# Controler_2_25.net
KiCad netlist of a schematic drawn in EAGLE
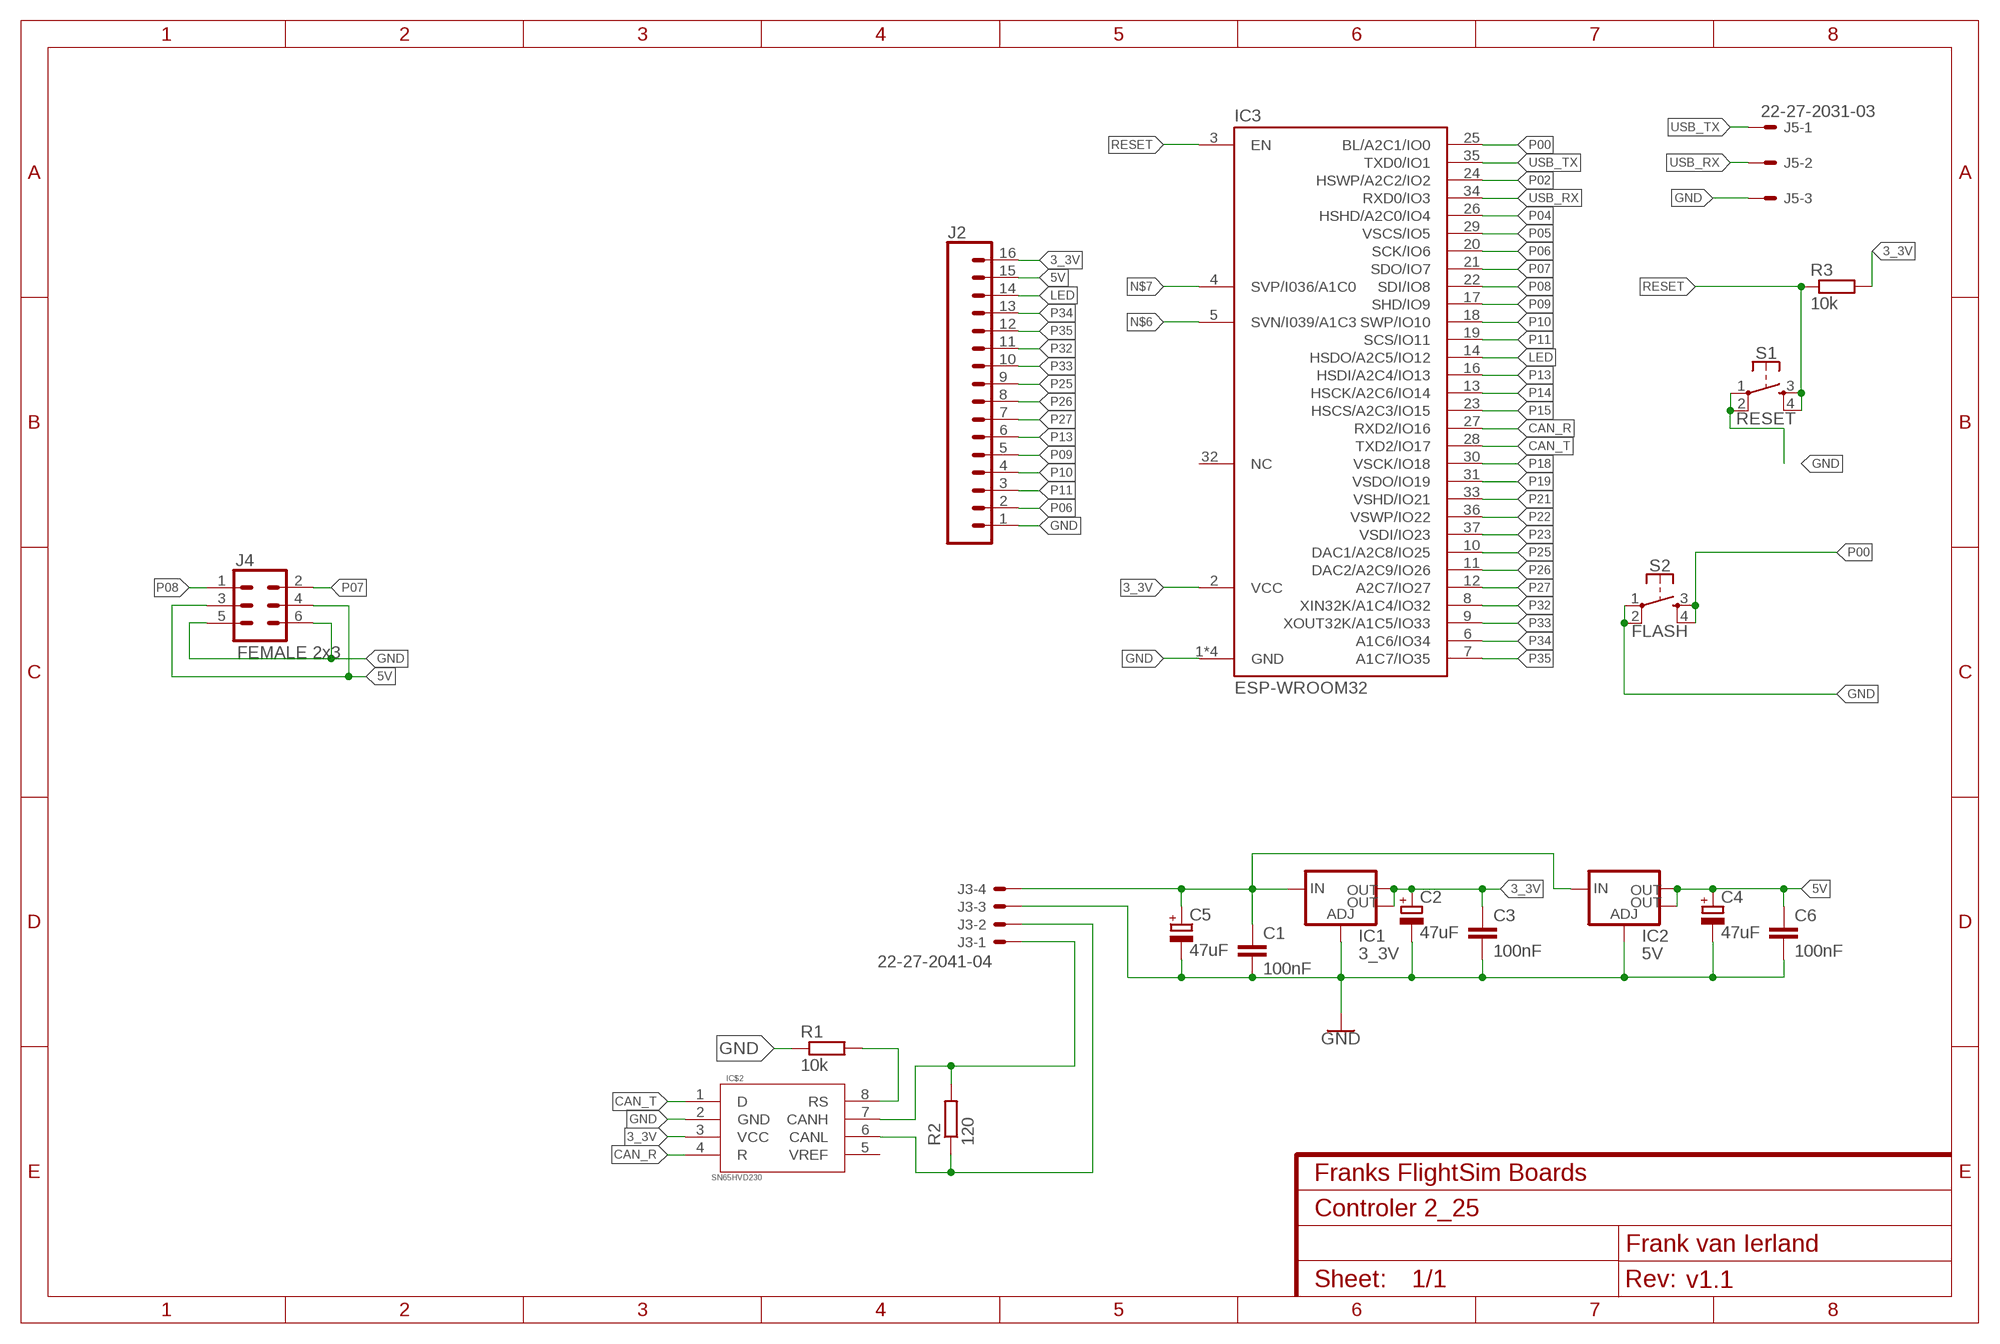
[diagram p0: schematic, sheet 1]

(export (version "E")
  (design (tool "Eeschema 10.0.6"))
  (components
    (comp (ref "C1")
      (value "100nF")
      (footprint "eagle-import:C1206")
      (libsource (lib "eagle-import") (part "C-EUC1206"))
    )
    (comp (ref "C2")
      (value "47uF")
      (footprint "eagle-import:CT3528")
      (libsource (lib "eagle-import") (part "CPOL-EUCT3528"))
    )
    (comp (ref "C3")
      (value "100nF")
      (footprint "eagle-import:C1206")
      (libsource (lib "eagle-import") (part "C-EUC1206"))
    )
    (comp (ref "C4")
      (value "47uF")
      (footprint "eagle-import:CT3528")
      (libsource (lib "eagle-import") (part "CPOL-EUCT3528"))
    )
    (comp (ref "C5")
      (value "47uF")
      (footprint "eagle-import:153CLV-0605")
      (libsource (lib "eagle-import") (part "CPOL-EU153CLV-0605"))
    )
    (comp (ref "C6")
      (value "100nF")
      (footprint "eagle-import:C1206")
      (libsource (lib "eagle-import") (part "C-EUC1206"))
    )
    (comp (ref "IC$2")
      (value "SN65HVD230")
      (footprint "eagle-import:SO08")
      (libsource (lib "eagle-import") (part "SN65HVD230"))
    )
    (comp (ref "IC1")
      (value "3_3V")
      (footprint "eagle-import:SOT223")
      (libsource (lib "eagle-import") (part "V_REG_LM1117SOT223"))
    )
    (comp (ref "IC2")
      (value "5V")
      (footprint "eagle-import:SOT223")
      (libsource (lib "eagle-import") (part "V_REG_LM1117SOT223"))
    )
    (comp (ref "IC3")
      (value "ESP-WROOM32")
      (footprint "eagle-import:ESP-WROOM32")
      (libsource (lib "eagle-import") (part "ESP-WROOM32"))
    )
    (comp (ref "J2")
      (value "CONN_16")
      (footprint "eagle-import:1X16")
      (libsource (lib "eagle-import") (part "CONN_16"))
    )
    (comp (ref "J3")
      (value "22-27-2041-04")
      (footprint "eagle-import:6410-04")
      (fields (field (name "MF") "MOLEX"))
      (libsource (lib "eagle-import") (part "22-?-0427-2041"))
    )
    (comp (ref "J4")
      (value "FEMALE 2x3")
      (footprint "eagle-import:2X3")
      (libsource (lib "eagle-import") (part "CONN_03X2FEMALE"))
    )
    (comp (ref "J5")
      (value "22-27-2031-03")
      (footprint "eagle-import:6410-03")
      (fields (field (name "MF") "MOLEX"))
      (libsource (lib "eagle-import") (part "22-?-0327-2031"))
    )
    (comp (ref "R1")
      (value "10k")
      (footprint "eagle-import:M1206")
      (libsource (lib "eagle-import") (part "R-EU_M1206"))
    )
    (comp (ref "R2")
      (value "120")
      (footprint "eagle-import:R1210")
      (libsource (lib "eagle-import") (part "R-EU_R1210"))
    )
    (comp (ref "R3")
      (value "10k")
      (footprint "eagle-import:M1206")
      (libsource (lib "eagle-import") (part "R-EU_M1206"))
    )
    (comp (ref "S1")
      (value "RESET")
      (footprint "eagle-import:TACTILE_SWITCH_SMD_4.6X2.8MM")
      (libsource (lib "eagle-import") (part "MOMENTARY-SWITCH-SPST-2-SMD-4.6X2.8MM"))
    )
    (comp (ref "S2")
      (value "FLASH")
      (footprint "eagle-import:TACTILE_SWITCH_SMD_4.6X2.8MM")
      (libsource (lib "eagle-import") (part "MOMENTARY-SWITCH-SPST-2-SMD-4.6X2.8MM"))
    )
  )
  (nets
    (net (code "1") (name "3_3V") (class "Default")
      (node (ref "C2") (pin "-") (pinfunction "+_-") (pintype "passive"))
      (node (ref "C3") (pin "1") (pinfunction "1_1") (pintype "passive"))
      (node (ref "IC$2") (pin "3") (pinfunction "VCC_3") (pintype "bidirectional"))
      (node (ref "IC1") (pin "2") (pinfunction "OUT_2") (pintype "output"))
      (node (ref "IC1") (pin "4") (pinfunction "OUT_4") (pintype "output"))
      (node (ref "IC3") (pin "2") (pinfunction "VCC_2") (pintype "power_in"))
      (node (ref "J2") (pin "16") (pinfunction "16_16") (pintype "passive"))
      (node (ref "R3") (pin "2") (pinfunction "2_2") (pintype "passive"))
    )
    (net (code "2") (name "5V") (class "Default")
      (node (ref "C4") (pin "-") (pinfunction "+_-") (pintype "passive"))
      (node (ref "C6") (pin "1") (pinfunction "1_1") (pintype "passive"))
      (node (ref "IC2") (pin "2") (pinfunction "OUT_2") (pintype "output"))
      (node (ref "IC2") (pin "4") (pinfunction "OUT_4") (pintype "output"))
      (node (ref "J2") (pin "15") (pinfunction "15_15") (pintype "passive"))
      (node (ref "J4") (pin "3") (pinfunction "3_3") (pintype "bidirectional"))
      (node (ref "J4") (pin "4") (pinfunction "4_4") (pintype "bidirectional"))
    )
    (net (code "3") (name "CAN_R") (class "Default")
      (node (ref "IC$2") (pin "4") (pinfunction "R_4") (pintype "bidirectional"))
      (node (ref "IC3") (pin "27") (pinfunction "RXD2/IO16_27") (pintype "bidirectional"))
    )
    (net (code "4") (name "CAN_T") (class "Default")
      (node (ref "IC$2") (pin "1") (pinfunction "D_1") (pintype "bidirectional"))
      (node (ref "IC3") (pin "28") (pinfunction "TXD2/IO17_28") (pintype "bidirectional"))
    )
    (net (code "5") (name "GND") (class "Default")
      (node (ref "C1") (pin "2") (pinfunction "2_2") (pintype "passive"))
      (node (ref "C2") (pin "+") (pinfunction "-_+") (pintype "passive"))
      (node (ref "C3") (pin "2") (pinfunction "2_2") (pintype "passive"))
      (node (ref "C4") (pin "+") (pinfunction "-_+") (pintype "passive"))
      (node (ref "C5") (pin "-") (pinfunction "-_-") (pintype "passive"))
      (node (ref "C6") (pin "2") (pinfunction "2_2") (pintype "passive"))
      (node (ref "IC$2") (pin "2") (pinfunction "GND_2") (pintype "bidirectional"))
      (node (ref "IC1") (pin "1") (pinfunction "ADJ_1") (pintype "input"))
      (node (ref "IC2") (pin "1") (pinfunction "ADJ_1") (pintype "input"))
      (node (ref "IC3") (pin "1") (pinfunction "GND_1") (pintype "power_in"))
      (node (ref "IC3") (pin "15") (pinfunction "GND_15") (pintype "power_in"))
      (node (ref "IC3") (pin "38") (pinfunction "GND_38") (pintype "power_in"))
      (node (ref "IC3") (pin "TP") (pinfunction "GND_TP") (pintype "power_in"))
      (node (ref "J2") (pin "1") (pinfunction "1_1") (pintype "passive"))
      (node (ref "J3") (pin "3") (pinfunction "S_3") (pintype "passive"))
      (node (ref "J4") (pin "5") (pinfunction "5_5") (pintype "bidirectional"))
      (node (ref "J4") (pin "6") (pinfunction "6_6") (pintype "bidirectional"))
      (node (ref "J5") (pin "3") (pinfunction "S_3") (pintype "passive"))
      (node (ref "R1") (pin "1") (pinfunction "1_1") (pintype "passive"))
      (node (ref "S1") (pin "1") (pinfunction "1_1") (pintype "passive"))
      (node (ref "S1") (pin "2") (pinfunction "2_2") (pintype "passive"))
      (node (ref "S2") (pin "1") (pinfunction "1_1") (pintype "passive"))
      (node (ref "S2") (pin "2") (pinfunction "2_2") (pintype "passive"))
    )
    (net (code "6") (name "LED") (class "Default")
      (node (ref "IC3") (pin "14") (pinfunction "HSDO/A2C5/IO12_14") (pintype "bidirectional"))
      (node (ref "J2") (pin "14") (pinfunction "14_14") (pintype "passive"))
    )
    (net (code "7") (name "N$6") (class "Default")
      (node (ref "IC3") (pin "5") (pinfunction "SVN/I039/A1C3_5") (pintype "bidirectional"))
    )
    (net (code "8") (name "N$7") (class "Default")
      (node (ref "IC3") (pin "4") (pinfunction "SVP/I036/A1C0_4") (pintype "bidirectional"))
    )
    (net (code "9") (name "Net-(IC$2-CANH)") (class "Default")
      (node (ref "IC$2") (pin "7") (pinfunction "CANH_7") (pintype "bidirectional"))
      (node (ref "J3") (pin "1") (pinfunction "S_1") (pintype "passive"))
      (node (ref "R2") (pin "2") (pinfunction "2_2") (pintype "passive"))
    )
    (net (code "10") (name "Net-(IC$2-CANL)") (class "Default")
      (node (ref "IC$2") (pin "6") (pinfunction "CANL_6") (pintype "bidirectional"))
      (node (ref "J3") (pin "2") (pinfunction "S_2") (pintype "passive"))
      (node (ref "R2") (pin "1") (pinfunction "1_1") (pintype "passive"))
    )
    (net (code "11") (name "Net-(IC$2-RS)") (class "Default")
      (node (ref "IC$2") (pin "8") (pinfunction "RS_8") (pintype "bidirectional"))
      (node (ref "R1") (pin "2") (pinfunction "2_2") (pintype "passive"))
    )
    (net (code "12") (name "Net-(IC1-IN)") (class "Default")
      (node (ref "C1") (pin "1") (pinfunction "1_1") (pintype "passive"))
      (node (ref "C5") (pin "+") (pinfunction "+_+") (pintype "passive"))
      (node (ref "IC1") (pin "3") (pinfunction "IN_3") (pintype "input"))
      (node (ref "IC2") (pin "3") (pinfunction "IN_3") (pintype "input"))
      (node (ref "J3") (pin "4") (pinfunction "S_4") (pintype "passive"))
    )
    (net (code "13") (name "P00") (class "Default")
      (node (ref "IC3") (pin "25") (pinfunction "BL/A2C1/IO0_25") (pintype "bidirectional"))
      (node (ref "S2") (pin "3") (pinfunction "3_3") (pintype "passive"))
      (node (ref "S2") (pin "4") (pinfunction "4_4") (pintype "passive"))
    )
    (net (code "14") (name "P02") (class "Default")
      (node (ref "IC3") (pin "24") (pinfunction "HSWP/A2C2/IO2_24") (pintype "bidirectional"))
    )
    (net (code "15") (name "P04") (class "Default")
      (node (ref "IC3") (pin "26") (pinfunction "HSHD/A2C0/IO4_26") (pintype "bidirectional"))
    )
    (net (code "16") (name "P05") (class "Default")
      (node (ref "IC3") (pin "29") (pinfunction "VSCS/IO5_29") (pintype "bidirectional"))
    )
    (net (code "17") (name "P06") (class "Default")
      (node (ref "IC3") (pin "20") (pinfunction "SCK/IO6_20") (pintype "bidirectional"))
      (node (ref "J2") (pin "2") (pinfunction "2_2") (pintype "passive"))
    )
    (net (code "18") (name "P07") (class "Default")
      (node (ref "IC3") (pin "21") (pinfunction "SDO/IO7_21") (pintype "bidirectional"))
      (node (ref "J4") (pin "2") (pinfunction "2_2") (pintype "bidirectional"))
    )
    (net (code "19") (name "P08") (class "Default")
      (node (ref "IC3") (pin "22") (pinfunction "SDI/IO8_22") (pintype "bidirectional"))
      (node (ref "J4") (pin "1") (pinfunction "1_1") (pintype "bidirectional"))
    )
    (net (code "20") (name "P09") (class "Default")
      (node (ref "IC3") (pin "17") (pinfunction "SHD/IO9_17") (pintype "bidirectional"))
      (node (ref "J2") (pin "5") (pinfunction "5_5") (pintype "passive"))
    )
    (net (code "21") (name "P10") (class "Default")
      (node (ref "IC3") (pin "18") (pinfunction "SWP/IO10_18") (pintype "bidirectional"))
      (node (ref "J2") (pin "4") (pinfunction "4_4") (pintype "passive"))
    )
    (net (code "22") (name "P11") (class "Default")
      (node (ref "IC3") (pin "19") (pinfunction "SCS/IO11_19") (pintype "bidirectional"))
      (node (ref "J2") (pin "3") (pinfunction "3_3") (pintype "passive"))
    )
    (net (code "23") (name "P13") (class "Default")
      (node (ref "IC3") (pin "16") (pinfunction "HSDI/A2C4/IO13_16") (pintype "bidirectional"))
      (node (ref "J2") (pin "6") (pinfunction "6_6") (pintype "passive"))
    )
    (net (code "24") (name "P14") (class "Default")
      (node (ref "IC3") (pin "13") (pinfunction "HSCK/A2C6/IO14_13") (pintype "bidirectional"))
    )
    (net (code "25") (name "P15") (class "Default")
      (node (ref "IC3") (pin "23") (pinfunction "HSCS/A2C3/IO15_23") (pintype "bidirectional"))
    )
    (net (code "26") (name "P18") (class "Default")
      (node (ref "IC3") (pin "30") (pinfunction "VSCK/IO18_30") (pintype "bidirectional"))
    )
    (net (code "27") (name "P19") (class "Default")
      (node (ref "IC3") (pin "31") (pinfunction "VSDO/IO19_31") (pintype "bidirectional"))
    )
    (net (code "28") (name "P21") (class "Default")
      (node (ref "IC3") (pin "33") (pinfunction "VSHD/IO21_33") (pintype "bidirectional"))
    )
    (net (code "29") (name "P22") (class "Default")
      (node (ref "IC3") (pin "36") (pinfunction "VSWP/IO22_36") (pintype "bidirectional"))
    )
    (net (code "30") (name "P23") (class "Default")
      (node (ref "IC3") (pin "37") (pinfunction "VSDI/IO23_37") (pintype "bidirectional"))
    )
    (net (code "31") (name "P25") (class "Default")
      (node (ref "IC3") (pin "10") (pinfunction "DAC1/A2C8/IO25_10") (pintype "bidirectional"))
      (node (ref "J2") (pin "9") (pinfunction "9_9") (pintype "passive"))
    )
    (net (code "32") (name "P26") (class "Default")
      (node (ref "IC3") (pin "11") (pinfunction "DAC2/A2C9/IO26_11") (pintype "bidirectional"))
      (node (ref "J2") (pin "8") (pinfunction "8_8") (pintype "passive"))
    )
    (net (code "33") (name "P27") (class "Default")
      (node (ref "IC3") (pin "12") (pinfunction "A2C7/IO27_12") (pintype "bidirectional"))
      (node (ref "J2") (pin "7") (pinfunction "7_7") (pintype "passive"))
    )
    (net (code "34") (name "P32") (class "Default")
      (node (ref "IC3") (pin "8") (pinfunction "XIN32K/A1C4/IO32_8") (pintype "bidirectional"))
      (node (ref "J2") (pin "11") (pinfunction "11_11") (pintype "passive"))
    )
    (net (code "35") (name "P33") (class "Default")
      (node (ref "IC3") (pin "9") (pinfunction "XOUT32K/A1C5/IO33_9") (pintype "bidirectional"))
      (node (ref "J2") (pin "10") (pinfunction "10_10") (pintype "passive"))
    )
    (net (code "36") (name "P34") (class "Default")
      (node (ref "IC3") (pin "6") (pinfunction "A1C6/IO34_6") (pintype "bidirectional"))
      (node (ref "J2") (pin "13") (pinfunction "13_13") (pintype "passive"))
    )
    (net (code "37") (name "P35") (class "Default")
      (node (ref "IC3") (pin "7") (pinfunction "A1C7/IO35_7") (pintype "bidirectional"))
      (node (ref "J2") (pin "12") (pinfunction "12_12") (pintype "passive"))
    )
    (net (code "38") (name "RESET") (class "Default")
      (node (ref "IC3") (pin "3") (pinfunction "EN_3") (pintype "bidirectional"))
      (node (ref "R3") (pin "1") (pinfunction "1_1") (pintype "passive"))
      (node (ref "S1") (pin "3") (pinfunction "3_3") (pintype "passive"))
      (node (ref "S1") (pin "4") (pinfunction "4_4") (pintype "passive"))
    )
    (net (code "39") (name "USB_RX") (class "Default")
      (node (ref "IC3") (pin "34") (pinfunction "RXD0/IO3_34") (pintype "bidirectional"))
      (node (ref "J5") (pin "2") (pinfunction "S_2") (pintype "passive"))
    )
    (net (code "40") (name "USB_TX") (class "Default")
      (node (ref "IC3") (pin "35") (pinfunction "TXD0/IO1_35") (pintype "bidirectional"))
      (node (ref "J5") (pin "1") (pinfunction "S_1") (pintype "passive"))
    )
    (net (code "41") (name "unconnected-(IC$2-VREF-Pad5)") (class "Default")
      (node (ref "IC$2") (pin "5") (pinfunction "VREF_5") (pintype "bidirectional"))
    )
    (net (code "42") (name "unconnected-(IC3-NC-Pad32)") (class "Default")
      (node (ref "IC3") (pin "32") (pinfunction "NC_32") (pintype "bidirectional"))
    )
  )
)
